# usbtrng.net
KiCad netlist of a schematic drawn in EAGLE
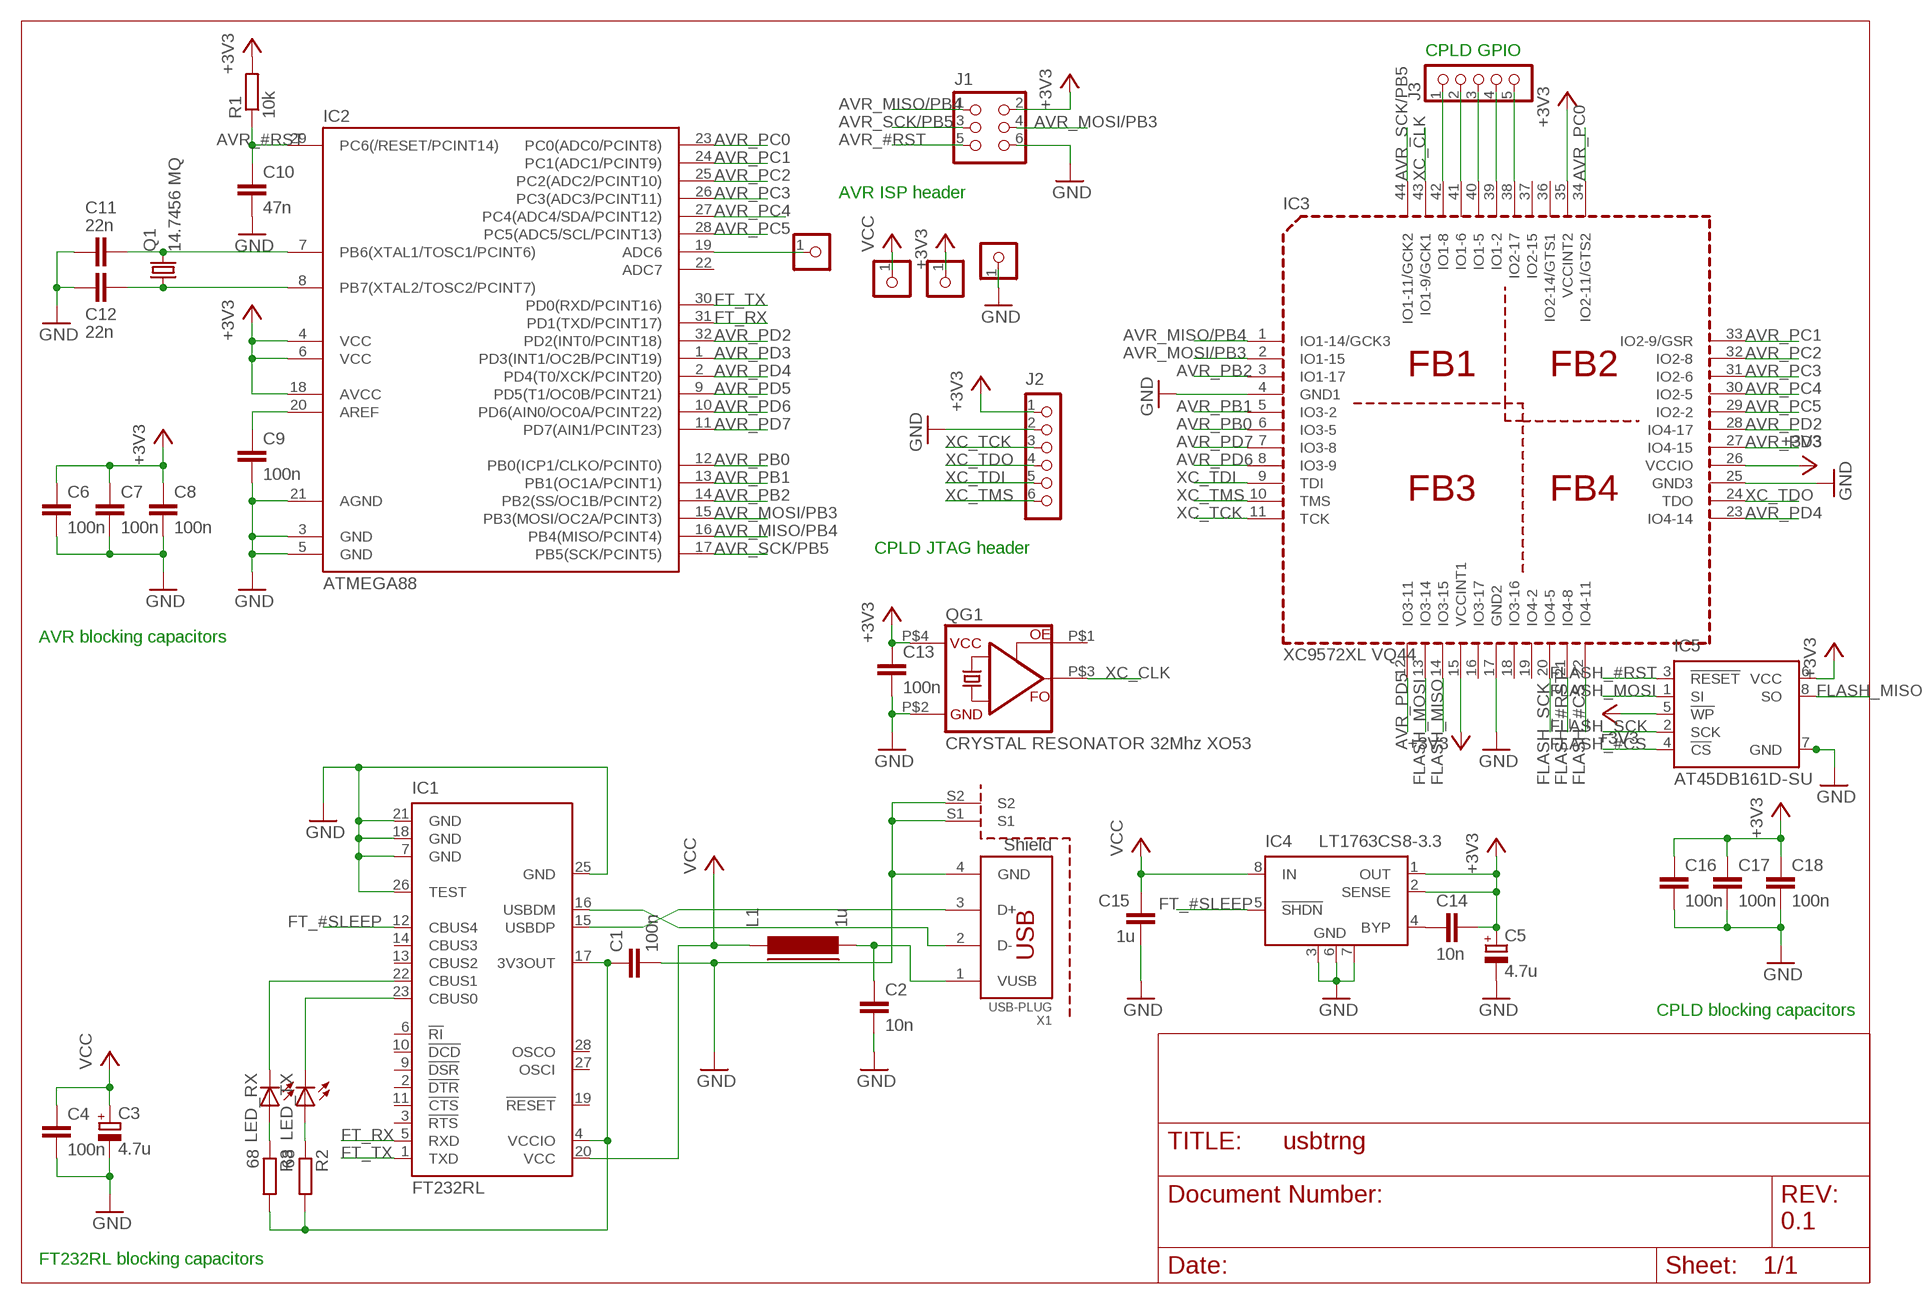
[diagram p0: schematic, sheet 1]

(export (version "E")
  (design (tool "Eeschema 10.0.6"))
  (components
    (comp (ref "C1")
      (value "100n")
      (footprint "eagle-import:C0805")
      (libsource (lib "eagle-import") (part "C-EUC0805"))
    )
    (comp (ref "C2")
      (value "10n")
      (footprint "eagle-import:C0805")
      (libsource (lib "eagle-import") (part "C-EUC0805"))
    )
    (comp (ref "C3")
      (value "4.7u")
      (footprint "eagle-import:PANASONIC_B")
      (libsource (lib "eagle-import") (part "CPOL-EUB"))
    )
    (comp (ref "C4")
      (value "100n")
      (footprint "eagle-import:C0805")
      (libsource (lib "eagle-import") (part "C-EUC0805"))
    )
    (comp (ref "C5")
      (value "4.7u")
      (footprint "eagle-import:PANASONIC_B")
      (libsource (lib "eagle-import") (part "CPOL-EUB"))
    )
    (comp (ref "C6")
      (value "100n")
      (footprint "eagle-import:C0805")
      (libsource (lib "eagle-import") (part "C-EUC0805"))
    )
    (comp (ref "C7")
      (value "100n")
      (footprint "eagle-import:C0805")
      (libsource (lib "eagle-import") (part "C-EUC0805"))
    )
    (comp (ref "C8")
      (value "100n")
      (footprint "eagle-import:C0805")
      (libsource (lib "eagle-import") (part "C-EUC0805"))
    )
    (comp (ref "C9")
      (value "100n")
      (footprint "eagle-import:C0805")
      (libsource (lib "eagle-import") (part "C-EUC0805"))
    )
    (comp (ref "C10")
      (value "47n")
      (footprint "eagle-import:C0805")
      (libsource (lib "eagle-import") (part "C-EUC0805"))
    )
    (comp (ref "C11")
      (value "22n")
      (footprint "eagle-import:C0805")
      (libsource (lib "eagle-import") (part "C-EUC0805"))
    )
    (comp (ref "C12")
      (value "22n")
      (footprint "eagle-import:C0805")
      (libsource (lib "eagle-import") (part "C-EUC0805"))
    )
    (comp (ref "C13")
      (value "100n")
      (footprint "eagle-import:C0805")
      (libsource (lib "eagle-import") (part "C-EUC0805"))
    )
    (comp (ref "C14")
      (value "10n")
      (footprint "eagle-import:C0805")
      (libsource (lib "eagle-import") (part "C-EUC0805"))
    )
    (comp (ref "C15")
      (value "1u")
      (footprint "eagle-import:C0805")
      (libsource (lib "eagle-import") (part "C-EUC0805"))
    )
    (comp (ref "C16")
      (value "100n")
      (footprint "eagle-import:C0805")
      (libsource (lib "eagle-import") (part "C-EUC0805"))
    )
    (comp (ref "C17")
      (value "100n")
      (footprint "eagle-import:C0805")
      (libsource (lib "eagle-import") (part "C-EUC0805"))
    )
    (comp (ref "C18")
      (value "100n")
      (footprint "eagle-import:C0805")
      (libsource (lib "eagle-import") (part "C-EUC0805"))
    )
    (comp (ref "IC1")
      (value "FT232RL")
      (footprint "eagle-import:SSOP28")
      (libsource (lib "eagle-import") (part "FT232RL"))
    )
    (comp (ref "IC2")
      (value "ATMEGA88")
      (footprint "eagle-import:TQFP32-08")
      (libsource (lib "eagle-import") (part "ATMEGA48/88/168-AU"))
    )
    (comp (ref "IC3")
      (value "XC9572XL VQ44")
      (footprint "eagle-import:VQ-44")
      (libsource (lib "eagle-import") (part "IC_CPLD_XC9572VQ44"))
    )
    (comp (ref "IC4")
      (value "LT1763CS8-3.3")
      (footprint "eagle-import:SOIC8")
      (libsource (lib "eagle-import") (part "LT1763CS8-3.3"))
    )
    (comp (ref "IC5")
      (value "AT45DB161D-SU")
      (footprint "eagle-import:8S2")
      (fields (field (name "MF") "ATMEL"))
      (libsource (lib "eagle-import") (part "AT45DB161D-SU"))
    )
    (comp (ref "J1")
      (value "CON_HEADER_2X03-PTH")
      (footprint "eagle-import:M2X3")
      (libsource (lib "eagle-import") (part "CON_HEADER_2X03-PTH"))
    )
    (comp (ref "J2")
      (value "CON_HEADER_1X06-PTH")
      (footprint "eagle-import:M1X6")
      (libsource (lib "eagle-import") (part "CON_HEADER_1X06-PTH"))
    )
    (comp (ref "J3")
      (value "CON_HEADER_1X05-PTH")
      (footprint "eagle-import:M1X5")
      (libsource (lib "eagle-import") (part "CON_HEADER_1X05-PTH"))
    )
    (comp (ref "J4")
      (value "CON_HEADER_1X01-PTH")
      (footprint "eagle-import:M1X1")
      (libsource (lib "eagle-import") (part "CON_HEADER_1X01-PTH"))
    )
    (comp (ref "J5")
      (value "CON_HEADER_1X01-PTH")
      (footprint "eagle-import:M1X1")
      (libsource (lib "eagle-import") (part "CON_HEADER_1X01-PTH"))
    )
    (comp (ref "J7")
      (value "CON_HEADER_1X01-PTH")
      (footprint "eagle-import:M1X1")
      (libsource (lib "eagle-import") (part "CON_HEADER_1X01-PTH"))
    )
    (comp (ref "J8")
      (value "CON_HEADER_1X01-PTH")
      (footprint "eagle-import:M1X1")
      (libsource (lib "eagle-import") (part "CON_HEADER_1X01-PTH"))
    )
    (comp (ref "L1")
      (value "1u")
      (footprint "eagle-import:FB805")
      (libsource (lib "eagle-import") (part "FERRITE-0805"))
    )
    (comp (ref "LED_RX")
      (value "LEDCHIP-LED0805")
      (footprint "eagle-import:CHIP-LED0805")
      (libsource (lib "eagle-import") (part "LEDCHIP-LED0805"))
    )
    (comp (ref "LED_TX")
      (value "LEDCHIP-LED0805")
      (footprint "eagle-import:CHIP-LED0805")
      (libsource (lib "eagle-import") (part "LEDCHIP-LED0805"))
    )
    (comp (ref "Q1")
      (value "14.7456 MQ")
      (footprint "eagle-import:MJ")
      (libsource (lib "eagle-import") (part "CRYSTALMJ"))
    )
    (comp (ref "QG1")
      (value "CRYSTAL RESONATOR 32Mhz XO53")
      (footprint "eagle-import:XO53")
      (libsource (lib "eagle-import") (part "CRYSTALRESONATORXO53"))
    )
    (comp (ref "R1")
      (value "10k")
      (footprint "eagle-import:M0805")
      (libsource (lib "eagle-import") (part "R-EU_M0805"))
    )
    (comp (ref "R2")
      (value "68")
      (footprint "eagle-import:M0805")
      (libsource (lib "eagle-import") (part "R-EU_M0805"))
    )
    (comp (ref "R3")
      (value "68")
      (footprint "eagle-import:M0805")
      (libsource (lib "eagle-import") (part "R-EU_M0805"))
    )
    (comp (ref "X1")
      (value "USB-PLUG")
      (footprint "eagle-import:USB-PLUG-A-SMD-2S")
      (libsource (lib "eagle-import") (part "USB-1X-2S-PLUG-A-SMD"))
    )
  )
  (nets
    (net (code "1") (name "+3V3") (class "Default")
      (node (ref "C13") (pin "1") (pinfunction "1_1") (pintype "passive"))
      (node (ref "C14") (pin "2") (pinfunction "2_2") (pintype "passive"))
      (node (ref "C16") (pin "1") (pinfunction "1_1") (pintype "passive"))
      (node (ref "C17") (pin "1") (pinfunction "1_1") (pintype "passive"))
      (node (ref "C18") (pin "1") (pinfunction "1_1") (pintype "passive"))
      (node (ref "C5") (pin "+") (pinfunction "+_+") (pintype "passive"))
      (node (ref "C6") (pin "1") (pinfunction "1_1") (pintype "passive"))
      (node (ref "C7") (pin "1") (pinfunction "1_1") (pintype "passive"))
      (node (ref "C8") (pin "1") (pinfunction "1_1") (pintype "passive"))
      (node (ref "IC2") (pin "18") (pinfunction "AVCC_18") (pintype "passive"))
      (node (ref "IC2") (pin "4") (pinfunction "VCC_4") (pintype "power_in"))
      (node (ref "IC2") (pin "6") (pinfunction "VCC_6") (pintype "power_in"))
      (node (ref "IC3") (pin "15") (pinfunction "VCCINT1_15") (pintype "bidirectional"))
      (node (ref "IC3") (pin "26") (pinfunction "VCCIO_26") (pintype "bidirectional"))
      (node (ref "IC3") (pin "35") (pinfunction "VCCINT2_35") (pintype "bidirectional"))
      (node (ref "IC4") (pin "1") (pinfunction "OUT_1") (pintype "passive"))
      (node (ref "IC4") (pin "2") (pinfunction "SENSE_2") (pintype "input"))
      (node (ref "IC5") (pin "5") (pinfunction "~{WP}_5") (pintype "input"))
      (node (ref "IC5") (pin "6") (pinfunction "VCC_6") (pintype "power_in"))
      (node (ref "J1") (pin "2") (pinfunction "2_2") (pintype "passive"))
      (node (ref "J2") (pin "1") (pinfunction "1_1") (pintype "bidirectional"))
      (node (ref "J7") (pin "1") (pinfunction "1_1") (pintype "passive"))
      (node (ref "QG1") (pin "P$4") (pinfunction "VCC_P$4") (pintype "power_in"))
      (node (ref "R1") (pin "2") (pinfunction "2_2") (pintype "passive"))
    )
    (net (code "2") (name "/AVR_#RST") (class "Default")
      (node (ref "C10") (pin "1") (pinfunction "1_1") (pintype "passive"))
      (node (ref "IC2") (pin "29") (pinfunction "PC6(/RESET/PCINT14)_29") (pintype "bidirectional"))
      (node (ref "J1") (pin "5") (pinfunction "5_5") (pintype "passive"))
      (node (ref "R1") (pin "1") (pinfunction "1_1") (pintype "passive"))
    )
    (net (code "3") (name "/AVR_MISO{slash}PB4") (class "Default")
      (node (ref "IC2") (pin "16") (pinfunction "PB4(MISO/PCINT4)_16") (pintype "bidirectional"))
      (node (ref "IC3") (pin "1") (pinfunction "IO1-14/GCK3_1") (pintype "bidirectional"))
      (node (ref "J1") (pin "1") (pinfunction "1_1") (pintype "passive"))
    )
    (net (code "4") (name "/AVR_MOSI{slash}PB3") (class "Default")
      (node (ref "IC2") (pin "15") (pinfunction "PB3(MOSI/OC2A/PCINT3)_15") (pintype "bidirectional"))
      (node (ref "IC3") (pin "2") (pinfunction "IO1-15_2") (pintype "bidirectional"))
      (node (ref "J1") (pin "4") (pinfunction "4_4") (pintype "passive"))
    )
    (net (code "5") (name "/AVR_PB0") (class "Default")
      (node (ref "IC2") (pin "12") (pinfunction "PB0(ICP1/CLKO/PCINT0)_12") (pintype "bidirectional"))
      (node (ref "IC3") (pin "6") (pinfunction "IO3-5_6") (pintype "bidirectional"))
    )
    (net (code "6") (name "/AVR_PB1") (class "Default")
      (node (ref "IC2") (pin "13") (pinfunction "PB1(OC1A/PCINT1)_13") (pintype "bidirectional"))
      (node (ref "IC3") (pin "5") (pinfunction "IO3-2_5") (pintype "bidirectional"))
    )
    (net (code "7") (name "/AVR_PB2") (class "Default")
      (node (ref "IC2") (pin "14") (pinfunction "PB2(SS/OC1B/PCINT2)_14") (pintype "bidirectional"))
      (node (ref "IC3") (pin "3") (pinfunction "IO1-17_3") (pintype "bidirectional"))
    )
    (net (code "8") (name "/AVR_PC0") (class "Default")
      (node (ref "IC2") (pin "23") (pinfunction "PC0(ADC0/PCINT8)_23") (pintype "bidirectional"))
      (node (ref "IC3") (pin "34") (pinfunction "IO2-11/GTS2_34") (pintype "bidirectional"))
    )
    (net (code "9") (name "/AVR_PC1") (class "Default")
      (node (ref "IC2") (pin "24") (pinfunction "PC1(ADC1/PCINT9)_24") (pintype "bidirectional"))
      (node (ref "IC3") (pin "33") (pinfunction "IO2-9/GSR_33") (pintype "bidirectional"))
    )
    (net (code "10") (name "/AVR_PC2") (class "Default")
      (node (ref "IC2") (pin "25") (pinfunction "PC2(ADC2/PCINT10)_25") (pintype "bidirectional"))
      (node (ref "IC3") (pin "32") (pinfunction "IO2-8_32") (pintype "bidirectional"))
    )
    (net (code "11") (name "/AVR_PC3") (class "Default")
      (node (ref "IC2") (pin "26") (pinfunction "PC3(ADC3/PCINT11)_26") (pintype "bidirectional"))
      (node (ref "IC3") (pin "31") (pinfunction "IO2-6_31") (pintype "bidirectional"))
    )
    (net (code "12") (name "/AVR_PC4") (class "Default")
      (node (ref "IC2") (pin "27") (pinfunction "PC4(ADC4/SDA/PCINT12)_27") (pintype "bidirectional"))
      (node (ref "IC3") (pin "30") (pinfunction "IO2-5_30") (pintype "bidirectional"))
    )
    (net (code "13") (name "/AVR_PC5") (class "Default")
      (node (ref "IC2") (pin "28") (pinfunction "PC5(ADC5/SCL/PCINT13)_28") (pintype "bidirectional"))
      (node (ref "IC3") (pin "29") (pinfunction "IO2-2_29") (pintype "bidirectional"))
    )
    (net (code "14") (name "/AVR_PD2") (class "Default")
      (node (ref "IC2") (pin "32") (pinfunction "PD2(INT0/PCINT18)_32") (pintype "bidirectional"))
      (node (ref "IC3") (pin "28") (pinfunction "IO4-17_28") (pintype "bidirectional"))
    )
    (net (code "15") (name "/AVR_PD3") (class "Default")
      (node (ref "IC2") (pin "1") (pinfunction "PD3(INT1/OC2B/PCINT19)_1") (pintype "bidirectional"))
      (node (ref "IC3") (pin "27") (pinfunction "IO4-15_27") (pintype "bidirectional"))
    )
    (net (code "16") (name "/AVR_PD4") (class "Default")
      (node (ref "IC2") (pin "2") (pinfunction "PD4(T0/XCK/PCINT20)_2") (pintype "bidirectional"))
      (node (ref "IC3") (pin "23") (pinfunction "IO4-14_23") (pintype "bidirectional"))
    )
    (net (code "17") (name "/AVR_PD5") (class "Default")
      (node (ref "IC2") (pin "9") (pinfunction "PD5(T1/OC0B/PCINT21)_9") (pintype "bidirectional"))
      (node (ref "IC3") (pin "12") (pinfunction "IO3-11_12") (pintype "bidirectional"))
    )
    (net (code "18") (name "/AVR_PD6") (class "Default")
      (node (ref "IC2") (pin "10") (pinfunction "PD6(AIN0/OC0A/PCINT22)_10") (pintype "bidirectional"))
      (node (ref "IC3") (pin "8") (pinfunction "IO3-9_8") (pintype "bidirectional"))
    )
    (net (code "19") (name "/AVR_PD7") (class "Default")
      (node (ref "IC2") (pin "11") (pinfunction "PD7(AIN1/PCINT23)_11") (pintype "bidirectional"))
      (node (ref "IC3") (pin "7") (pinfunction "IO3-8_7") (pintype "bidirectional"))
    )
    (net (code "20") (name "/AVR_SCK{slash}PB5") (class "Default")
      (node (ref "IC2") (pin "17") (pinfunction "PB5(SCK/PCINT5)_17") (pintype "bidirectional"))
      (node (ref "IC3") (pin "44") (pinfunction "IO1-11/GCK2_44") (pintype "bidirectional"))
      (node (ref "J1") (pin "3") (pinfunction "3_3") (pintype "passive"))
    )
    (net (code "21") (name "/FLASH_#CS") (class "Default")
      (node (ref "IC3") (pin "22") (pinfunction "IO4-11_22") (pintype "bidirectional"))
      (node (ref "IC5") (pin "4") (pinfunction "~{CS}_4") (pintype "input"))
    )
    (net (code "22") (name "/FLASH_#RST") (class "Default")
      (node (ref "IC3") (pin "21") (pinfunction "IO4-8_21") (pintype "bidirectional"))
      (node (ref "IC5") (pin "3") (pinfunction "~{RESET}_3") (pintype "input"))
    )
    (net (code "23") (name "/FLASH_MISO") (class "Default")
      (node (ref "IC3") (pin "14") (pinfunction "IO3-15_14") (pintype "bidirectional"))
      (node (ref "IC5") (pin "8") (pinfunction "SO_8") (pintype "output"))
    )
    (net (code "24") (name "/FLASH_MOSI") (class "Default")
      (node (ref "IC3") (pin "13") (pinfunction "IO3-14_13") (pintype "bidirectional"))
      (node (ref "IC5") (pin "1") (pinfunction "SI_1") (pintype "input"))
    )
    (net (code "25") (name "/FLASH_SCK") (class "Default")
      (node (ref "IC3") (pin "20") (pinfunction "IO4-5_20") (pintype "bidirectional"))
      (node (ref "IC5") (pin "2") (pinfunction "SCK_2") (pintype "input"))
    )
    (net (code "26") (name "/FT_#SLEEP") (class "Default")
      (node (ref "IC1") (pin "12") (pinfunction "CBUS4_12") (pintype "bidirectional"))
      (node (ref "IC4") (pin "5") (pinfunction "~{SHDN}_5") (pintype "input"))
    )
    (net (code "27") (name "/FT_RX") (class "Default")
      (node (ref "IC1") (pin "5") (pinfunction "RXD_5") (pintype "input"))
      (node (ref "IC2") (pin "31") (pinfunction "PD1(TXD/PCINT17)_31") (pintype "bidirectional"))
    )
    (net (code "28") (name "/FT_TX") (class "Default")
      (node (ref "IC1") (pin "1") (pinfunction "TXD_1") (pintype "output"))
      (node (ref "IC2") (pin "30") (pinfunction "PD0(RXD/PCINT16)_30") (pintype "bidirectional"))
    )
    (net (code "29") (name "/XC_CLK") (class "Default")
      (node (ref "IC3") (pin "43") (pinfunction "IO1-9/GCK1_43") (pintype "bidirectional"))
      (node (ref "QG1") (pin "P$3") (pinfunction "FO_P$3") (pintype "output"))
    )
    (net (code "30") (name "/XC_TCK") (class "Default")
      (node (ref "IC3") (pin "11") (pinfunction "TCK_11") (pintype "bidirectional"))
      (node (ref "J2") (pin "3") (pinfunction "3_3") (pintype "passive"))
    )
    (net (code "31") (name "/XC_TDI") (class "Default")
      (node (ref "IC3") (pin "9") (pinfunction "TDI_9") (pintype "bidirectional"))
      (node (ref "J2") (pin "5") (pinfunction "5_5") (pintype "passive"))
    )
    (net (code "32") (name "/XC_TDO") (class "Default")
      (node (ref "IC3") (pin "24") (pinfunction "TDO_24") (pintype "bidirectional"))
      (node (ref "J2") (pin "4") (pinfunction "4_4") (pintype "passive"))
    )
    (net (code "33") (name "/XC_TMS") (class "Default")
      (node (ref "IC3") (pin "10") (pinfunction "TMS_10") (pintype "bidirectional"))
      (node (ref "J2") (pin "6") (pinfunction "6_6") (pintype "passive"))
    )
    (net (code "34") (name "GND") (class "Default")
      (node (ref "C1") (pin "2") (pinfunction "2_2") (pintype "passive"))
      (node (ref "C10") (pin "2") (pinfunction "2_2") (pintype "passive"))
      (node (ref "C11") (pin "1") (pinfunction "1_1") (pintype "passive"))
      (node (ref "C12") (pin "1") (pinfunction "1_1") (pintype "passive"))
      (node (ref "C13") (pin "2") (pinfunction "2_2") (pintype "passive"))
      (node (ref "C15") (pin "1") (pinfunction "1_1") (pintype "passive"))
      (node (ref "C16") (pin "2") (pinfunction "2_2") (pintype "passive"))
      (node (ref "C17") (pin "2") (pinfunction "2_2") (pintype "passive"))
      (node (ref "C18") (pin "2") (pinfunction "2_2") (pintype "passive"))
      (node (ref "C2") (pin "2") (pinfunction "2_2") (pintype "passive"))
      (node (ref "C3") (pin "-") (pinfunction "-_-") (pintype "passive"))
      (node (ref "C4") (pin "2") (pinfunction "2_2") (pintype "passive"))
      (node (ref "C5") (pin "-") (pinfunction "-_-") (pintype "passive"))
      (node (ref "C6") (pin "2") (pinfunction "2_2") (pintype "passive"))
      (node (ref "C7") (pin "2") (pinfunction "2_2") (pintype "passive"))
      (node (ref "C8") (pin "2") (pinfunction "2_2") (pintype "passive"))
      (node (ref "C9") (pin "2") (pinfunction "2_2") (pintype "passive"))
      (node (ref "IC1") (pin "18") (pinfunction "GND_18") (pintype "power_in"))
      (node (ref "IC1") (pin "21") (pinfunction "GND_21") (pintype "power_in"))
      (node (ref "IC1") (pin "25") (pinfunction "GND_25") (pintype "power_in"))
      (node (ref "IC1") (pin "26") (pinfunction "TEST_26") (pintype "input"))
      (node (ref "IC1") (pin "7") (pinfunction "GND_7") (pintype "power_in"))
      (node (ref "IC2") (pin "21") (pinfunction "AGND_21") (pintype "power_in"))
      (node (ref "IC2") (pin "3") (pinfunction "GND_3") (pintype "power_in"))
      (node (ref "IC2") (pin "5") (pinfunction "GND_5") (pintype "power_in"))
      (node (ref "IC3") (pin "17") (pinfunction "GND2_17") (pintype "bidirectional"))
      (node (ref "IC3") (pin "25") (pinfunction "GND3_25") (pintype "bidirectional"))
      (node (ref "IC3") (pin "4") (pinfunction "GND1_4") (pintype "bidirectional"))
      (node (ref "IC4") (pin "3") (pinfunction "GND_3") (pintype "power_in"))
      (node (ref "IC4") (pin "6") (pinfunction "GND_6") (pintype "power_in"))
      (node (ref "IC4") (pin "7") (pinfunction "GND_7") (pintype "power_in"))
      (node (ref "IC5") (pin "7") (pinfunction "GND_7") (pintype "power_in"))
      (node (ref "J1") (pin "6") (pinfunction "6_6") (pintype "passive"))
      (node (ref "J2") (pin "2") (pinfunction "2_2") (pintype "bidirectional"))
      (node (ref "J5") (pin "1") (pinfunction "1_1") (pintype "passive"))
      (node (ref "QG1") (pin "P$2") (pinfunction "GND_P$2") (pintype "power_in"))
      (node (ref "X1") (pin "4") (pinfunction "GND_4") (pintype "passive"))
      (node (ref "X1") (pin "S1") (pinfunction "S1_S1") (pintype "passive"))
      (node (ref "X1") (pin "S2") (pinfunction "S2_S2") (pintype "passive"))
    )
    (net (code "35") (name "Net-(IC1-3V3OUT)") (class "Default")
      (node (ref "C1") (pin "1") (pinfunction "1_1") (pintype "passive"))
      (node (ref "IC1") (pin "17") (pinfunction "3V3OUT_17") (pintype "output"))
      (node (ref "IC1") (pin "4") (pinfunction "VCCIO_4") (pintype "power_in"))
      (node (ref "R2") (pin "2") (pinfunction "2_2") (pintype "passive"))
      (node (ref "R3") (pin "2") (pinfunction "2_2") (pintype "passive"))
    )
    (net (code "36") (name "Net-(IC1-CBUS0)") (class "Default")
      (node (ref "IC1") (pin "23") (pinfunction "CBUS0_23") (pintype "bidirectional"))
      (node (ref "LED_TX") (pin "C") (pinfunction "C_C") (pintype "passive"))
    )
    (net (code "37") (name "Net-(IC1-CBUS1)") (class "Default")
      (node (ref "IC1") (pin "22") (pinfunction "CBUS1_22") (pintype "bidirectional"))
      (node (ref "LED_RX") (pin "C") (pinfunction "C_C") (pintype "passive"))
    )
    (net (code "38") (name "Net-(IC1-USBDM)") (class "Default")
      (node (ref "IC1") (pin "16") (pinfunction "USBDM_16") (pintype "bidirectional"))
      (node (ref "X1") (pin "2") (pinfunction "D-_2") (pintype "passive"))
    )
    (net (code "39") (name "Net-(IC1-USBDP)") (class "Default")
      (node (ref "IC1") (pin "15") (pinfunction "USBDP_15") (pintype "bidirectional"))
      (node (ref "X1") (pin "3") (pinfunction "D+_3") (pintype "passive"))
    )
    (net (code "40") (name "Net-(IC2-ADC6)") (class "Default")
      (node (ref "IC2") (pin "19") (pinfunction "ADC6_19") (pintype "passive"))
      (node (ref "J4") (pin "1") (pinfunction "1_1") (pintype "passive"))
    )
    (net (code "41") (name "Net-(IC2-AREF)") (class "Default")
      (node (ref "C9") (pin "1") (pinfunction "1_1") (pintype "passive"))
      (node (ref "IC2") (pin "20") (pinfunction "AREF_20") (pintype "passive"))
    )
    (net (code "42") (name "Net-(IC2-PB6(XTAL1{slash}TOSC1{slash}PCINT6))") (class "Default")
      (node (ref "C11") (pin "2") (pinfunction "2_2") (pintype "passive"))
      (node (ref "IC2") (pin "7") (pinfunction "PB6(XTAL1/TOSC1/PCINT6)_7") (pintype "bidirectional"))
      (node (ref "Q1") (pin "P3") (pinfunction "2_P3") (pintype "passive"))
    )
    (net (code "43") (name "Net-(IC2-PB7(XTAL2{slash}TOSC2{slash}PCINT7))") (class "Default")
      (node (ref "C12") (pin "2") (pinfunction "2_2") (pintype "passive"))
      (node (ref "IC2") (pin "8") (pinfunction "PB7(XTAL2/TOSC2/PCINT7)_8") (pintype "bidirectional"))
      (node (ref "Q1") (pin "P1") (pinfunction "1_P1") (pintype "passive"))
    )
    (net (code "44") (name "Net-(IC3-IO1-2)") (class "Default")
      (node (ref "IC3") (pin "39") (pinfunction "IO1-2_39") (pintype "bidirectional"))
      (node (ref "J3") (pin "4") (pinfunction "4_4") (pintype "bidirectional"))
    )
    (net (code "45") (name "Net-(IC3-IO1-5)") (class "Default")
      (node (ref "IC3") (pin "40") (pinfunction "IO1-5_40") (pintype "bidirectional"))
      (node (ref "J3") (pin "3") (pinfunction "3_3") (pintype "bidirectional"))
    )
    (net (code "46") (name "Net-(IC3-IO1-6)") (class "Default")
      (node (ref "IC3") (pin "41") (pinfunction "IO1-6_41") (pintype "bidirectional"))
      (node (ref "J3") (pin "2") (pinfunction "2_2") (pintype "bidirectional"))
    )
    (net (code "47") (name "Net-(IC3-IO1-8)") (class "Default")
      (node (ref "IC3") (pin "42") (pinfunction "IO1-8_42") (pintype "bidirectional"))
      (node (ref "J3") (pin "1") (pinfunction "1_1") (pintype "bidirectional"))
    )
    (net (code "48") (name "Net-(IC3-IO2-17)") (class "Default")
      (node (ref "IC3") (pin "38") (pinfunction "IO2-17_38") (pintype "bidirectional"))
      (node (ref "J3") (pin "5") (pinfunction "5_5") (pintype "bidirectional"))
    )
    (net (code "49") (name "Net-(IC4-BYP)") (class "Default")
      (node (ref "C14") (pin "1") (pinfunction "1_1") (pintype "passive"))
      (node (ref "IC4") (pin "4") (pinfunction "BYP_4") (pintype "input"))
    )
    (net (code "50") (name "Net-(LED_RX-PadA)") (class "Default")
      (node (ref "LED_RX") (pin "A") (pinfunction "A_A") (pintype "passive"))
      (node (ref "R3") (pin "1") (pinfunction "1_1") (pintype "passive"))
    )
    (net (code "51") (name "Net-(LED_TX-PadA)") (class "Default")
      (node (ref "LED_TX") (pin "A") (pinfunction "A_A") (pintype "passive"))
      (node (ref "R2") (pin "1") (pinfunction "1_1") (pintype "passive"))
    )
    (net (code "52") (name "Net-(X1-VUSB)") (class "Default")
      (node (ref "C2") (pin "1") (pinfunction "1_1") (pintype "passive"))
      (node (ref "L1") (pin "2") (pinfunction "2_2") (pintype "passive"))
      (node (ref "X1") (pin "1") (pinfunction "VUSB_1") (pintype "passive"))
    )
    (net (code "53") (name "VCC") (class "Default")
      (node (ref "C15") (pin "2") (pinfunction "2_2") (pintype "passive"))
      (node (ref "C3") (pin "+") (pinfunction "+_+") (pintype "passive"))
      (node (ref "C4") (pin "1") (pinfunction "1_1") (pintype "passive"))
      (node (ref "IC1") (pin "20") (pinfunction "VCC_20") (pintype "power_in"))
      (node (ref "IC4") (pin "8") (pinfunction "IN_8") (pintype "input"))
      (node (ref "J8") (pin "1") (pinfunction "1_1") (pintype "passive"))
      (node (ref "L1") (pin "1") (pinfunction "1_1") (pintype "passive"))
    )
    (net (code "54") (name "unconnected-(IC1-CBUS2-Pad13)") (class "Default")
      (node (ref "IC1") (pin "13") (pinfunction "CBUS2_13") (pintype "bidirectional"))
    )
    (net (code "55") (name "unconnected-(IC1-CBUS3-Pad14)") (class "Default")
      (node (ref "IC1") (pin "14") (pinfunction "CBUS3_14") (pintype "bidirectional"))
    )
    (net (code "56") (name "unconnected-(IC1-OSCI-Pad27)") (class "Default")
      (node (ref "IC1") (pin "27") (pinfunction "OSCI_27") (pintype "input"))
    )
    (net (code "57") (name "unconnected-(IC1-OSCO-Pad28)") (class "Default")
      (node (ref "IC1") (pin "28") (pinfunction "OSCO_28") (pintype "output"))
    )
    (net (code "58") (name "unconnected-(IC1-~{CTS}-Pad11)") (class "Default")
      (node (ref "IC1") (pin "11") (pinfunction "~{CTS}_11") (pintype "input"))
    )
    (net (code "59") (name "unconnected-(IC1-~{DCD}-Pad10)") (class "Default")
      (node (ref "IC1") (pin "10") (pinfunction "~{DCD}_10") (pintype "input"))
    )
    (net (code "60") (name "unconnected-(IC1-~{DSR}-Pad9)") (class "Default")
      (node (ref "IC1") (pin "9") (pinfunction "~{DSR}_9") (pintype "input"))
    )
    (net (code "61") (name "unconnected-(IC1-~{DTR}-Pad2)") (class "Default")
      (node (ref "IC1") (pin "2") (pinfunction "~{DTR}_2") (pintype "output"))
    )
    (net (code "62") (name "unconnected-(IC1-~{RESET}-Pad19)") (class "Default")
      (node (ref "IC1") (pin "19") (pinfunction "~{RESET}_19") (pintype "input"))
    )
    (net (code "63") (name "unconnected-(IC1-~{RI}-Pad6)") (class "Default")
      (node (ref "IC1") (pin "6") (pinfunction "~{RI}_6") (pintype "input"))
    )
    (net (code "64") (name "unconnected-(IC1-~{RTS}-Pad3)") (class "Default")
      (node (ref "IC1") (pin "3") (pinfunction "~{RTS}_3") (pintype "output"))
    )
    (net (code "65") (name "unconnected-(IC2-ADC7-Pad22)") (class "Default")
      (node (ref "IC2") (pin "22") (pinfunction "ADC7_22") (pintype "passive"))
    )
    (net (code "66") (name "unconnected-(IC3-IO2-14{slash}GTS1-Pad36)") (class "Default")
      (node (ref "IC3") (pin "36") (pinfunction "IO2-14/GTS1_36") (pintype "bidirectional"))
    )
    (net (code "67") (name "unconnected-(IC3-IO2-15-Pad37)") (class "Default")
      (node (ref "IC3") (pin "37") (pinfunction "IO2-15_37") (pintype "bidirectional"))
    )
    (net (code "68") (name "unconnected-(IC3-IO3-16-Pad18)") (class "Default")
      (node (ref "IC3") (pin "18") (pinfunction "IO3-16_18") (pintype "bidirectional"))
    )
    (net (code "69") (name "unconnected-(IC3-IO3-17-Pad16)") (class "Default")
      (node (ref "IC3") (pin "16") (pinfunction "IO3-17_16") (pintype "bidirectional"))
    )
    (net (code "70") (name "unconnected-(IC3-IO4-2-Pad19)") (class "Default")
      (node (ref "IC3") (pin "19") (pinfunction "IO4-2_19") (pintype "bidirectional"))
    )
    (net (code "71") (name "unconnected-(QG1-OE-PadP$1)") (class "Default")
      (node (ref "QG1") (pin "P$1") (pinfunction "OE_P$1") (pintype "input"))
    )
  )
)
